# Microcontroller.net
KiCad netlist of a schematic drawn in Altium Designer
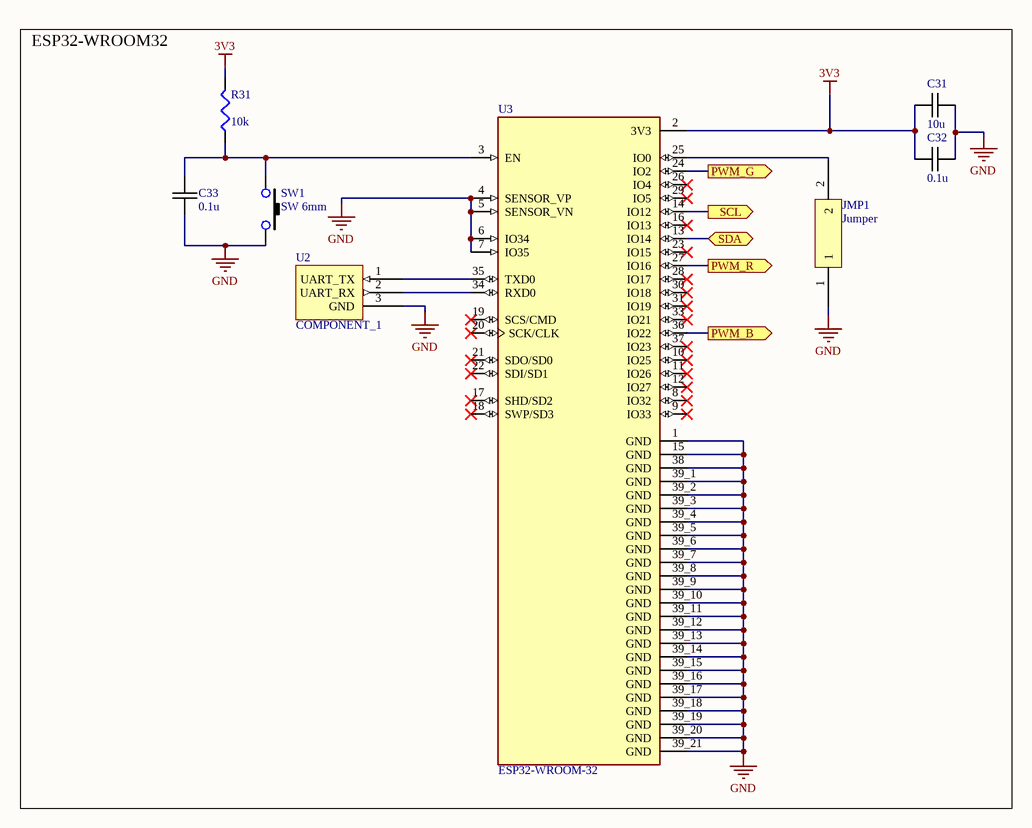
[diagram p0: Microcontroller.SchDoc]

(export (version "E")
  (design (tool "Eeschema 10.0.6"))
  (components
    (comp (ref "C31")
      (value "10u")
      (footprint "0603C-GENERIC")
      (description "GENERIC CAPACITOR NON POLARISED 0603")
      (libsource (lib "vh_altium_library") (part "C0603-GENERIC"))
    )
    (comp (ref "C32")
      (value "0.1u")
      (footprint "0603C-GENERIC")
      (description "GENERIC CAPACITOR NON POLARISED 0603")
      (libsource (lib "vh_altium_library") (part "C0603-GENERIC"))
    )
    (comp (ref "C33")
      (value "0.1u")
      (footprint "0603C-GENERIC")
      (description "GENERIC CAPACITOR NON POLARISED 0603")
      (libsource (lib "vh_altium_library") (part "C0603-GENERIC"))
    )
    (comp (ref "JMP1") (value "Jumper") (footprint "jumper") (libsource (lib "LSEL_Library") (part "Jumper")))
    (comp (ref "R31")
      (value "10k")
      (footprint "J1-0603")
      (description "Resistor")
      (fields (field (name "PUBLISHER") "Altium Limited"))
      (libsource (lib "Miscellaneous Devices") (part "Res3"))
    )
    (comp (ref "SW1")
      (value "SW 6mm")
      (footprint "SW-PB-SMD")
      (description "PUSHBUTTON SWITCH 6MM SMD")
      (libsource (lib "vh_altium_library") (part "SW-PB6MM-SMD"))
    )
    (comp (ref "U2")
      (value "COMPONENT_1")
      (footprint "PCBComponent_1")
      (libsource (lib "uart connector") (part "COMPONENT_1"))
    )
    (comp (ref "U3")
      (value "ESP32-WROOM-32")
      (footprint "ESP32")
      (description "Bluetooth, WiFi Transceiver Module 2.4GHz ~ 2.5GHz Surface Mount")
      (fields (field (name "MF") "Espressif Systems") (field (name "DIGI-KEY_PART_NUMBER") "1904-1010-1-ND"))
      (libsource (lib "LSEL_Library") (part "ESP32-WROOM-32"))
    )
  )
  (nets
    (net (code "1") (name "/PWM_B") (class "Default")
      (node (ref "U3") (pin "36") (pinfunction "IO22_36") (pintype "bidirectional"))
    )
    (net (code "2") (name "/PWM_G") (class "Default")
      (node (ref "U3") (pin "24") (pinfunction "IO2_24") (pintype "bidirectional"))
    )
    (net (code "3") (name "/PWM_R") (class "Default")
      (node (ref "U3") (pin "27") (pinfunction "IO16_27") (pintype "bidirectional"))
    )
    (net (code "4") (name "/SCL") (class "Default")
      (node (ref "U3") (pin "14") (pinfunction "IO12_14") (pintype "bidirectional"))
    )
    (net (code "5") (name "/SDA") (class "Default")
      (node (ref "U3") (pin "13") (pinfunction "IO14_13") (pintype "bidirectional"))
    )
    (net (code "6") (name "3V3") (class "Default")
      (node (ref "C31") (pin "1") (pintype "passive"))
      (node (ref "C32") (pin "1") (pintype "passive"))
      (node (ref "R31") (pin "2") (pinfunction "2_2") (pintype "passive"))
      (node (ref "U3") (pin "2") (pinfunction "3V3_2") (pintype "power_in"))
    )
    (net (code "7") (name "GND") (class "Default")
      (node (ref "C31") (pin "2") (pintype "passive"))
      (node (ref "C32") (pin "2") (pintype "passive"))
      (node (ref "C33") (pin "2") (pintype "passive"))
      (node (ref "JMP1") (pin "1") (pinfunction "1_1") (pintype "passive"))
      (node (ref "SW1") (pin "2") (pintype "passive"))
      (node (ref "U2") (pin "3") (pinfunction "GND_3") (pintype "power_in"))
      (node (ref "U3") (pin "1") (pinfunction "GND_1") (pintype "power_in"))
      (node (ref "U3") (pin "15") (pinfunction "GND_15") (pintype "power_in"))
      (node (ref "U3") (pin "38") (pinfunction "GND_38") (pintype "power_in"))
      (node (ref "U3") (pin "39_1") (pinfunction "GND_39_1") (pintype "power_in"))
      (node (ref "U3") (pin "39_10") (pinfunction "GND_39_10") (pintype "power_in"))
      (node (ref "U3") (pin "39_11") (pinfunction "GND_39_11") (pintype "power_in"))
      (node (ref "U3") (pin "39_12") (pinfunction "GND_39_12") (pintype "power_in"))
      (node (ref "U3") (pin "39_13") (pinfunction "GND_39_13") (pintype "power_in"))
      (node (ref "U3") (pin "39_14") (pinfunction "GND_39_14") (pintype "power_in"))
      (node (ref "U3") (pin "39_15") (pinfunction "GND_39_15") (pintype "power_in"))
      (node (ref "U3") (pin "39_16") (pinfunction "GND_39_16") (pintype "power_in"))
      (node (ref "U3") (pin "39_17") (pinfunction "GND_39_17") (pintype "power_in"))
      (node (ref "U3") (pin "39_18") (pinfunction "GND_39_18") (pintype "power_in"))
      (node (ref "U3") (pin "39_19") (pinfunction "GND_39_19") (pintype "power_in"))
      (node (ref "U3") (pin "39_2") (pinfunction "GND_39_2") (pintype "power_in"))
      (node (ref "U3") (pin "39_20") (pinfunction "GND_39_20") (pintype "power_in"))
      (node (ref "U3") (pin "39_21") (pinfunction "GND_39_21") (pintype "power_in"))
      (node (ref "U3") (pin "39_3") (pinfunction "GND_39_3") (pintype "power_in"))
      (node (ref "U3") (pin "39_4") (pinfunction "GND_39_4") (pintype "power_in"))
      (node (ref "U3") (pin "39_5") (pinfunction "GND_39_5") (pintype "power_in"))
      (node (ref "U3") (pin "39_6") (pinfunction "GND_39_6") (pintype "power_in"))
      (node (ref "U3") (pin "39_7") (pinfunction "GND_39_7") (pintype "power_in"))
      (node (ref "U3") (pin "39_8") (pinfunction "GND_39_8") (pintype "power_in"))
      (node (ref "U3") (pin "39_9") (pinfunction "GND_39_9") (pintype "power_in"))
      (node (ref "U3") (pin "4") (pinfunction "SENSOR_VP_4") (pintype "input"))
      (node (ref "U3") (pin "5") (pinfunction "SENSOR_VN_5") (pintype "input"))
      (node (ref "U3") (pin "6") (pinfunction "IO34_6") (pintype "input"))
      (node (ref "U3") (pin "7") (pinfunction "IO35_7") (pintype "input"))
    )
    (net (code "8") (name "Net-(U2-UART_RX)") (class "Default")
      (node (ref "U2") (pin "2") (pinfunction "UART_RX_2") (pintype "output"))
      (node (ref "U3") (pin "34") (pinfunction "RXD0_34") (pintype "bidirectional"))
    )
    (net (code "9") (name "Net-(U2-UART_TX)") (class "Default")
      (node (ref "U2") (pin "1") (pinfunction "UART_TX_1") (pintype "input"))
      (node (ref "U3") (pin "35") (pinfunction "TXD0_35") (pintype "bidirectional"))
    )
    (net (code "10") (name "Net-(U3-EN)") (class "Default")
      (node (ref "C33") (pin "1") (pintype "passive"))
      (node (ref "R31") (pin "1") (pinfunction "1_1") (pintype "passive"))
      (node (ref "SW1") (pin "1") (pintype "passive"))
      (node (ref "U3") (pin "3") (pinfunction "EN_3") (pintype "input"))
    )
    (net (code "11") (name "Net-(U3-IO0)") (class "Default")
      (node (ref "JMP1") (pin "2") (pinfunction "2_2") (pintype "passive"))
      (node (ref "U3") (pin "25") (pinfunction "IO0_25") (pintype "bidirectional"))
    )
    (net (code "12") (name "unconnected-(U3-IO4-Pad26)") (class "Default")
      (node (ref "U3") (pin "26") (pinfunction "IO4_26") (pintype "bidirectional+no_connect"))
    )
    (net (code "13") (name "unconnected-(U3-IO5-Pad29)") (class "Default")
      (node (ref "U3") (pin "29") (pinfunction "IO5_29") (pintype "bidirectional+no_connect"))
    )
    (net (code "14") (name "unconnected-(U3-IO13-Pad16)") (class "Default")
      (node (ref "U3") (pin "16") (pinfunction "IO13_16") (pintype "bidirectional+no_connect"))
    )
    (net (code "15") (name "unconnected-(U3-IO15-Pad23)") (class "Default")
      (node (ref "U3") (pin "23") (pinfunction "IO15_23") (pintype "bidirectional+no_connect"))
    )
    (net (code "16") (name "unconnected-(U3-IO17-Pad28)") (class "Default")
      (node (ref "U3") (pin "28") (pinfunction "IO17_28") (pintype "bidirectional+no_connect"))
    )
    (net (code "17") (name "unconnected-(U3-IO18-Pad30)") (class "Default")
      (node (ref "U3") (pin "30") (pinfunction "IO18_30") (pintype "bidirectional+no_connect"))
    )
    (net (code "18") (name "unconnected-(U3-IO19-Pad31)") (class "Default")
      (node (ref "U3") (pin "31") (pinfunction "IO19_31") (pintype "bidirectional+no_connect"))
    )
    (net (code "19") (name "unconnected-(U3-IO21-Pad33)") (class "Default")
      (node (ref "U3") (pin "33") (pinfunction "IO21_33") (pintype "bidirectional+no_connect"))
    )
    (net (code "20") (name "unconnected-(U3-IO23-Pad37)") (class "Default")
      (node (ref "U3") (pin "37") (pinfunction "IO23_37") (pintype "bidirectional+no_connect"))
    )
    (net (code "21") (name "unconnected-(U3-IO25-Pad10)") (class "Default")
      (node (ref "U3") (pin "10") (pinfunction "IO25_10") (pintype "bidirectional+no_connect"))
    )
    (net (code "22") (name "unconnected-(U3-IO26-Pad11)") (class "Default")
      (node (ref "U3") (pin "11") (pinfunction "IO26_11") (pintype "bidirectional+no_connect"))
    )
    (net (code "23") (name "unconnected-(U3-IO27-Pad12)") (class "Default")
      (node (ref "U3") (pin "12") (pinfunction "IO27_12") (pintype "bidirectional+no_connect"))
    )
    (net (code "24") (name "unconnected-(U3-IO32-Pad8)") (class "Default")
      (node (ref "U3") (pin "8") (pinfunction "IO32_8") (pintype "bidirectional+no_connect"))
    )
    (net (code "25") (name "unconnected-(U3-IO33-Pad9)") (class "Default")
      (node (ref "U3") (pin "9") (pinfunction "IO33_9") (pintype "bidirectional+no_connect"))
    )
    (net (code "26") (name "unconnected-(U3-SCK{slash}CLK-Pad20)") (class "Default")
      (node (ref "U3") (pin "20") (pinfunction "SCK/CLK_20") (pintype "bidirectional+no_connect"))
    )
    (net (code "27") (name "unconnected-(U3-SCS{slash}CMD-Pad19)") (class "Default")
      (node (ref "U3") (pin "19") (pinfunction "SCS/CMD_19") (pintype "bidirectional+no_connect"))
    )
    (net (code "28") (name "unconnected-(U3-SDI{slash}SD1-Pad22)") (class "Default")
      (node (ref "U3") (pin "22") (pinfunction "SDI/SD1_22") (pintype "bidirectional+no_connect"))
    )
    (net (code "29") (name "unconnected-(U3-SDO{slash}SD0-Pad21)") (class "Default")
      (node (ref "U3") (pin "21") (pinfunction "SDO/SD0_21") (pintype "bidirectional+no_connect"))
    )
    (net (code "30") (name "unconnected-(U3-SHD{slash}SD2-Pad17)") (class "Default")
      (node (ref "U3") (pin "17") (pinfunction "SHD/SD2_17") (pintype "bidirectional+no_connect"))
    )
    (net (code "31") (name "unconnected-(U3-SWP{slash}SD3-Pad18)") (class "Default")
      (node (ref "U3") (pin "18") (pinfunction "SWP/SD3_18") (pintype "bidirectional+no_connect"))
    )
  )
)
